# Qwiic_MP3.net
KiCad netlist of a schematic drawn in EAGLE
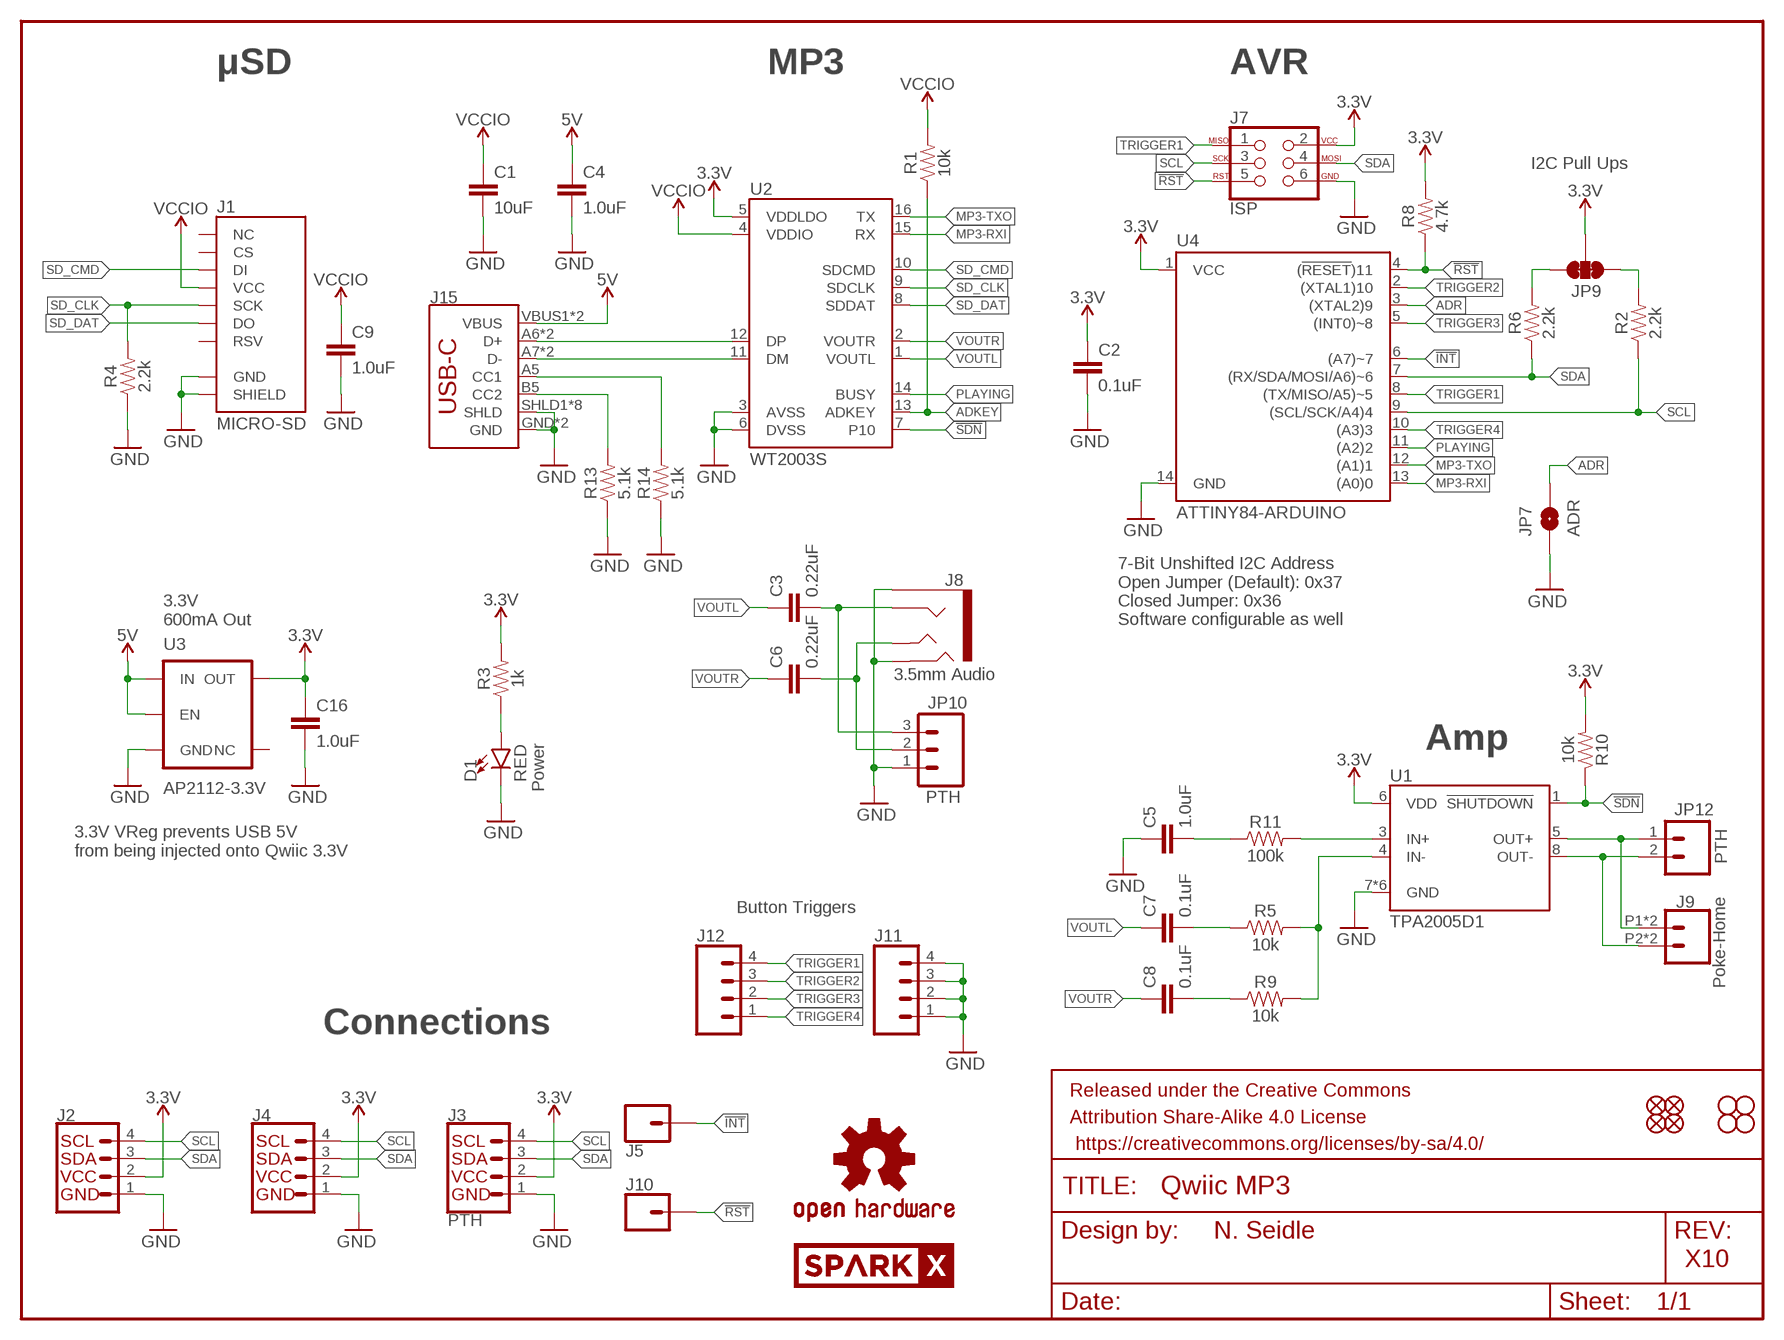
[diagram p0: schematic, sheet 1]

(export (version "E")
  (design (tool "Eeschema 10.0.6"))
  (components
    (comp (ref "C1")
      (value "10uF")
      (footprint "eagle-import:0603")
      (libsource (lib "eagle-import") (part "10UF-0603-6.3V-20%"))
    )
    (comp (ref "C2")
      (value "0.1uF")
      (footprint "eagle-import:0603")
      (libsource (lib "eagle-import") (part "0.1UF-0603-25V-(+80/-20%)"))
    )
    (comp (ref "C3")
      (value "0.22uF")
      (footprint "eagle-import:0603")
      (libsource (lib "eagle-import") (part "0.22UF-0603-25V-10%"))
    )
    (comp (ref "C4")
      (value "1.0uF")
      (footprint "eagle-import:0603")
      (libsource (lib "eagle-import") (part "1.0UF-0603-16V-10%"))
    )
    (comp (ref "C5")
      (value "1.0uF")
      (footprint "eagle-import:0603")
      (libsource (lib "eagle-import") (part "1.0UF-0603-16V-10%"))
    )
    (comp (ref "C6")
      (value "0.22uF")
      (footprint "eagle-import:0603")
      (libsource (lib "eagle-import") (part "0.22UF-0603-25V-10%"))
    )
    (comp (ref "C7")
      (value "0.1uF")
      (footprint "eagle-import:0603")
      (libsource (lib "eagle-import") (part "0.1UF-0603-25V-(+80/-20%)"))
    )
    (comp (ref "C8")
      (value "0.1uF")
      (footprint "eagle-import:0603")
      (libsource (lib "eagle-import") (part "0.1UF-0603-25V-(+80/-20%)"))
    )
    (comp (ref "C9")
      (value "1.0uF")
      (footprint "eagle-import:0603")
      (libsource (lib "eagle-import") (part "1.0UF-0603-16V-10%"))
    )
    (comp (ref "C16")
      (value "1.0uF")
      (footprint "eagle-import:0603")
      (libsource (lib "eagle-import") (part "1.0UF-0603-16V-10%"))
    )
    (comp (ref "D1")
      (value "RED")
      (footprint "eagle-import:LED-0603")
      (libsource (lib "eagle-import") (part "LED-RED0603"))
    )
    (comp (ref "FRAME1")
      (value "FRAME-LETTER")
      (footprint "eagle-import:CREATIVE_COMMONS")
      (libsource (lib "eagle-import") (part "FRAME-LETTER"))
    )
    (comp (ref "J1")
      (value "MICRO-SD")
      (footprint "eagle-import:MICRO-SD-SOCKET")
      (libsource (lib "eagle-import") (part "MICRO-SD_CARD_SOCKETPUSH-PUSH"))
    )
    (comp (ref "J2")
      (value "QWIIC_CONNECTORJS-1MM")
      (footprint "eagle-import:1X04_1MM_RA")
      (libsource (lib "eagle-import") (part "QWIIC_CONNECTORJS-1MM"))
    )
    (comp (ref "J3")
      (value "PTH")
      (footprint "eagle-import:1X04_NO_SILK")
      (libsource (lib "eagle-import") (part "I2C_STANDARD_NO_SILK"))
    )
    (comp (ref "J4")
      (value "QWIIC_CONNECTORJS-1MM")
      (footprint "eagle-import:1X04_1MM_RA")
      (libsource (lib "eagle-import") (part "QWIIC_CONNECTORJS-1MM"))
    )
    (comp (ref "J5")
      (value "CONN_01PTH_NO_SILK_YES_STOP")
      (footprint "eagle-import:1X01_NO_SILK")
      (libsource (lib "eagle-import") (part "CONN_01PTH_NO_SILK_YES_STOP"))
    )
    (comp (ref "J7")
      (value "ISP")
      (footprint "eagle-import:2X3_TEST_POINTS")
      (libsource (lib "eagle-import") (part "AVR_SPI_PROG_3X2TESTPOINTS"))
    )
    (comp (ref "J8")
      (value "3.5mm Audio")
      (footprint "eagle-import:AUDIO_JACK_3.5MM_TRRS_SMD_RA")
      (libsource (lib "eagle-import") (part "AUDIO_JACK_TRRSSMD_RA"))
    )
    (comp (ref "J9")
      (value "Poke-Home")
      (footprint "eagle-import:1X02_POKEHOME")
      (libsource (lib "eagle-import") (part "CONN_02SMALL_POKEHOME"))
    )
    (comp (ref "J10")
      (value "CONN_01PTH_NO_SILK_YES_STOP")
      (footprint "eagle-import:1X01_NO_SILK")
      (libsource (lib "eagle-import") (part "CONN_01PTH_NO_SILK_YES_STOP"))
    )
    (comp (ref "J11")
      (value "CONN_041X04_NO_SILK")
      (footprint "eagle-import:1X04_NO_SILK")
      (libsource (lib "eagle-import") (part "CONN_041X04_NO_SILK"))
    )
    (comp (ref "J12")
      (value "CONN_041X04_NO_SILK")
      (footprint "eagle-import:1X04_NO_SILK")
      (libsource (lib "eagle-import") (part "CONN_041X04_NO_SILK"))
    )
    (comp (ref "J15")
      (value "USB_C16PIN")
      (footprint "eagle-import:USB-C-16P")
      (libsource (lib "eagle-import") (part "USB_C16PIN"))
    )
    (comp (ref "JP1")
      (value "FIDUCIALUFIDUCIAL")
      (footprint "eagle-import:MICRO-FIDUCIAL")
      (libsource (lib "eagle-import") (part "FIDUCIALUFIDUCIAL"))
    )
    (comp (ref "JP2")
      (value "FIDUCIALUFIDUCIAL")
      (footprint "eagle-import:MICRO-FIDUCIAL")
      (libsource (lib "eagle-import") (part "FIDUCIALUFIDUCIAL"))
    )
    (comp (ref "JP3")
      (value "STAND-OFF")
      (footprint "eagle-import:STAND-OFF")
      (libsource (lib "eagle-import") (part "STAND-OFF"))
    )
    (comp (ref "JP4")
      (value "STAND-OFF")
      (footprint "eagle-import:STAND-OFF")
      (libsource (lib "eagle-import") (part "STAND-OFF"))
    )
    (comp (ref "JP5")
      (value "FIDUCIALUFIDUCIAL")
      (footprint "eagle-import:MICRO-FIDUCIAL")
      (libsource (lib "eagle-import") (part "FIDUCIALUFIDUCIAL"))
    )
    (comp (ref "JP6")
      (value "FIDUCIALUFIDUCIAL")
      (footprint "eagle-import:MICRO-FIDUCIAL")
      (libsource (lib "eagle-import") (part "FIDUCIALUFIDUCIAL"))
    )
    (comp (ref "JP7")
      (value "ADR")
      (footprint "eagle-import:SMT-JUMPER_2_NO_NO-SILK")
      (libsource (lib "eagle-import") (part "JUMPER-SMT_2_NO_NO-SILK"))
    )
    (comp (ref "JP9")
      (value "JUMPER-SMT_3_2-NC_TRACE_SILK")
      (footprint "eagle-import:SMT-JUMPER_3_2-NC_TRACE_SILK")
      (libsource (lib "eagle-import") (part "JUMPER-SMT_3_2-NC_TRACE_SILK"))
    )
    (comp (ref "JP10")
      (value "PTH")
      (footprint "eagle-import:1X03_NO_SILK")
      (libsource (lib "eagle-import") (part "CONN_031X03_NO_SILK"))
    )
    (comp (ref "JP11")
      (value "STAND-OFF")
      (footprint "eagle-import:STAND-OFF")
      (libsource (lib "eagle-import") (part "STAND-OFF"))
    )
    (comp (ref "JP12")
      (value "PTH")
      (footprint "eagle-import:1X02_NO_SILK")
      (libsource (lib "eagle-import") (part "CONN_021X02_NO_SILK"))
    )
    (comp (ref "JP13")
      (value "STAND-OFF")
      (footprint "eagle-import:STAND-OFF")
      (libsource (lib "eagle-import") (part "STAND-OFF"))
    )
    (comp (ref "LOGO1")
      (value "OSHW-LOGOMINI")
      (footprint "eagle-import:OSHW-LOGO-MINI")
      (libsource (lib "eagle-import") (part "OSHW-LOGOMINI"))
    )
    (comp (ref "R1")
      (value "10k")
      (footprint "eagle-import:0603")
      (libsource (lib "eagle-import") (part "10KOHM-0603-1/10W-1%"))
    )
    (comp (ref "R2")
      (value "2.2k")
      (footprint "eagle-import:0603")
      (libsource (lib "eagle-import") (part "2.2KOHM-0603-1/10W-1%"))
    )
    (comp (ref "R3")
      (value "1k")
      (footprint "eagle-import:0603")
      (libsource (lib "eagle-import") (part "1KOHM-0603-1/10W-1%"))
    )
    (comp (ref "R4")
      (value "2.2k")
      (footprint "eagle-import:0603")
      (libsource (lib "eagle-import") (part "2.2KOHM-0603-1/10W-1%"))
    )
    (comp (ref "R5")
      (value "10k")
      (footprint "eagle-import:0603")
      (libsource (lib "eagle-import") (part "10KOHM-0603-1/10W-1%"))
    )
    (comp (ref "R6")
      (value "2.2k")
      (footprint "eagle-import:0603")
      (libsource (lib "eagle-import") (part "2.2KOHM-0603-1/10W-1%"))
    )
    (comp (ref "R8")
      (value "4.7k")
      (footprint "eagle-import:0603")
      (libsource (lib "eagle-import") (part "4.7KOHM-0603-1/10W-1%"))
    )
    (comp (ref "R9")
      (value "10k")
      (footprint "eagle-import:0603")
      (libsource (lib "eagle-import") (part "10KOHM-0603-1/10W-1%"))
    )
    (comp (ref "R10")
      (value "10k")
      (footprint "eagle-import:0603")
      (libsource (lib "eagle-import") (part "10KOHM-0603-1/10W-1%"))
    )
    (comp (ref "R11")
      (value "100k")
      (footprint "eagle-import:0603")
      (libsource (lib "eagle-import") (part "100KOHM-0603-1/10W-1%"))
    )
    (comp (ref "R13")
      (value "5.1k")
      (footprint "eagle-import:0603")
      (libsource (lib "eagle-import") (part "5.1KOHM5.1KOHM-0603-1/10W-1%"))
    )
    (comp (ref "R14")
      (value "5.1k")
      (footprint "eagle-import:0603")
      (libsource (lib "eagle-import") (part "5.1KOHM5.1KOHM-0603-1/10W-1%"))
    )
    (comp (ref "U$1")
      (value "SPARKX-LOGO3")
      (footprint "eagle-import:SPARKX-SMALL")
      (libsource (lib "eagle-import") (part "SPARKX-LOGO3"))
    )
    (comp (ref "U$2")
      (value "SPARKX-LOGO4")
      (footprint "eagle-import:SPARKX-MEDIUM")
      (libsource (lib "eagle-import") (part "SPARKX-LOGO4"))
    )
    (comp (ref "U1")
      (value "TPA2005D1")
      (footprint "eagle-import:QFN-8_PAD")
      (libsource (lib "eagle-import") (part "TPA2005D1DRB"))
    )
    (comp (ref "U2")
      (value "WT2003S")
      (footprint "eagle-import:SO16")
      (libsource (lib "eagle-import") (part "WT2003S"))
    )
    (comp (ref "U3")
      (value "AP2112-3.3V")
      (footprint "eagle-import:SOT23-5")
      (libsource (lib "eagle-import") (part "V_REG_AP2112K-3.3V"))
    )
    (comp (ref "U4")
      (value "ATTINY84-ARDUINO")
      (footprint "eagle-import:SO14")
      (libsource (lib "eagle-import") (part "ATTINY84-ARDUINO"))
    )
  )
  (nets
    (net (code "1") (name "/~{INT}") (class "Default")
      (node (ref "J5") (pin "1") (pinfunction "1_1") (pintype "passive"))
      (node (ref "U4") (pin "6") (pinfunction "(A7)~{7}_6") (pintype "bidirectional"))
    )
    (net (code "2") (name "/~{RST}") (class "Default")
      (node (ref "J10") (pin "1") (pinfunction "1_1") (pintype "passive"))
      (node (ref "J7") (pin "5") (pinfunction "5_5") (pintype "passive"))
      (node (ref "R8") (pin "1") (pinfunction "1_1") (pintype "passive"))
      (node (ref "U4") (pin "4") (pinfunction "(~{RESET})11_4") (pintype "bidirectional"))
    )
    (net (code "3") (name "/~{SDN}") (class "Default")
      (node (ref "R10") (pin "1") (pinfunction "1_1") (pintype "passive"))
      (node (ref "U1") (pin "1") (pinfunction "~{SHUTDOWN}_1") (pintype "input"))
      (node (ref "U2") (pin "7") (pinfunction "P10_7") (pintype "bidirectional"))
    )
    (net (code "4") (name "3.3V") (class "Default")
      (node (ref "C16") (pin "1") (pinfunction "1_1") (pintype "passive"))
      (node (ref "C2") (pin "1") (pinfunction "1_1") (pintype "passive"))
      (node (ref "J2") (pin "2") (pinfunction "2_2") (pintype "power_in"))
      (node (ref "J3") (pin "2") (pinfunction "VCC_2") (pintype "power_in"))
      (node (ref "J4") (pin "2") (pinfunction "2_2") (pintype "power_in"))
      (node (ref "J7") (pin "2") (pinfunction "2_2") (pintype "passive"))
      (node (ref "JP9") (pin "2") (pinfunction "2_2") (pintype "passive"))
      (node (ref "R10") (pin "2") (pinfunction "2_2") (pintype "passive"))
      (node (ref "R3") (pin "2") (pinfunction "2_2") (pintype "passive"))
      (node (ref "R8") (pin "2") (pinfunction "2_2") (pintype "passive"))
      (node (ref "U1") (pin "6") (pinfunction "VDD_6") (pintype "power_in"))
      (node (ref "U2") (pin "5") (pinfunction "VDDLDO_5") (pintype "bidirectional"))
      (node (ref "U3") (pin "5") (pinfunction "OUT_5") (pintype "passive"))
      (node (ref "U4") (pin "1") (pinfunction "VCC_1") (pintype "bidirectional"))
    )
    (net (code "5") (name "5V") (class "Default")
      (node (ref "C4") (pin "1") (pinfunction "1_1") (pintype "passive"))
      (node (ref "J15") (pin "VBUS1") (pinfunction "VBUS_VBUS1") (pintype "bidirectional"))
      (node (ref "J15") (pin "VBUS2") (pinfunction "VBUS_VBUS2") (pintype "bidirectional"))
      (node (ref "U3") (pin "1") (pinfunction "IN_1") (pintype "input"))
      (node (ref "U3") (pin "3") (pinfunction "EN_3") (pintype "input"))
    )
    (net (code "6") (name "ADKEY") (class "Default")
      (node (ref "R1") (pin "1") (pinfunction "1_1") (pintype "passive"))
      (node (ref "U2") (pin "13") (pinfunction "ADKEY_13") (pintype "bidirectional"))
    )
    (net (code "7") (name "ADR") (class "Default")
      (node (ref "JP7") (pin "2") (pinfunction "2_2") (pintype "passive"))
      (node (ref "U4") (pin "3") (pinfunction "(XTAL2)9_3") (pintype "bidirectional"))
    )
    (net (code "8") (name "GND") (class "Default")
      (node (ref "C1") (pin "2") (pinfunction "2_2") (pintype "passive"))
      (node (ref "C16") (pin "2") (pinfunction "2_2") (pintype "passive"))
      (node (ref "C2") (pin "2") (pinfunction "2_2") (pintype "passive"))
      (node (ref "C4") (pin "2") (pinfunction "2_2") (pintype "passive"))
      (node (ref "C5") (pin "1") (pinfunction "1_1") (pintype "passive"))
      (node (ref "C9") (pin "2") (pinfunction "2_2") (pintype "passive"))
      (node (ref "D1") (pin "C") (pinfunction "C_C") (pintype "passive"))
      (node (ref "J1") (pin "CD1") (pinfunction "SHIELD_CD1") (pintype "bidirectional"))
      (node (ref "J1") (pin "GND") (pinfunction "GND_GND") (pintype "bidirectional"))
      (node (ref "J11") (pin "1") (pinfunction "1_1") (pintype "passive"))
      (node (ref "J11") (pin "2") (pinfunction "2_2") (pintype "passive"))
      (node (ref "J11") (pin "3") (pinfunction "3_3") (pintype "passive"))
      (node (ref "J11") (pin "4") (pinfunction "4_4") (pintype "passive"))
      (node (ref "J15") (pin "GND") (pinfunction "GND_GND") (pintype "bidirectional"))
      (node (ref "J15") (pin "GND2") (pinfunction "GND_GND2") (pintype "bidirectional"))
      (node (ref "J15") (pin "SHLD1") (pinfunction "SHLD_SHLD1") (pintype "bidirectional"))
      (node (ref "J15") (pin "SHLD2") (pinfunction "SHLD_SHLD2") (pintype "bidirectional"))
      (node (ref "J15") (pin "SHLD3") (pinfunction "SHLD_SHLD3") (pintype "bidirectional"))
      (node (ref "J15") (pin "SHLD4") (pinfunction "SHLD_SHLD4") (pintype "bidirectional"))
      (node (ref "J15") (pin "SHLD5") (pinfunction "SHLD_SHLD5") (pintype "bidirectional"))
      (node (ref "J15") (pin "SHLD6") (pinfunction "SHLD_SHLD6") (pintype "bidirectional"))
      (node (ref "J15") (pin "SHLD7") (pinfunction "SHLD_SHLD7") (pintype "bidirectional"))
      (node (ref "J15") (pin "SHLD8") (pinfunction "SHLD_SHLD8") (pintype "bidirectional"))
      (node (ref "J2") (pin "1") (pinfunction "1_1") (pintype "power_in"))
      (node (ref "J3") (pin "1") (pinfunction "GND_1") (pintype "power_in"))
      (node (ref "J4") (pin "1") (pinfunction "1_1") (pintype "power_in"))
      (node (ref "J7") (pin "6") (pinfunction "6_6") (pintype "passive"))
      (node (ref "J8") (pin "EARTH") (pinfunction "EARTH_EARTH") (pintype "bidirectional"))
      (node (ref "J8") (pin "RING2") (pinfunction "RING2_RING2") (pintype "bidirectional"))
      (node (ref "JP10") (pin "1") (pinfunction "1_1") (pintype "passive"))
      (node (ref "JP7") (pin "1") (pinfunction "1_1") (pintype "passive"))
      (node (ref "R13") (pin "1") (pinfunction "1_1") (pintype "passive"))
      (node (ref "R14") (pin "1") (pinfunction "1_1") (pintype "passive"))
      (node (ref "R4") (pin "1") (pinfunction "1_1") (pintype "passive"))
      (node (ref "U1") (pin "10") (pinfunction "GND_10") (pintype "power_in"))
      (node (ref "U1") (pin "11") (pinfunction "GND_11") (pintype "power_in"))
      (node (ref "U1") (pin "12") (pinfunction "GND_12") (pintype "power_in"))
      (node (ref "U1") (pin "13") (pinfunction "GND_13") (pintype "power_in"))
      (node (ref "U1") (pin "7") (pinfunction "GND_7") (pintype "power_in"))
      (node (ref "U1") (pin "9") (pinfunction "GND_9") (pintype "power_in"))
      (node (ref "U2") (pin "3") (pinfunction "AVSS_3") (pintype "bidirectional"))
      (node (ref "U2") (pin "6") (pinfunction "DVSS_6") (pintype "bidirectional"))
      (node (ref "U3") (pin "2") (pinfunction "GND_2") (pintype "input"))
      (node (ref "U4") (pin "14") (pinfunction "GND_14") (pintype "bidirectional"))
    )
    (net (code "9") (name "MP3-RXI") (class "Default")
      (node (ref "U2") (pin "15") (pinfunction "RX_15") (pintype "bidirectional"))
      (node (ref "U4") (pin "13") (pinfunction "(A0)0_13") (pintype "bidirectional"))
    )
    (net (code "10") (name "MP3-TXO") (class "Default")
      (node (ref "U2") (pin "16") (pinfunction "TX_16") (pintype "bidirectional"))
      (node (ref "U4") (pin "12") (pinfunction "(A1)1_12") (pintype "bidirectional"))
    )
    (net (code "11") (name "Net-(C3-Pad2)") (class "Default")
      (node (ref "C3") (pin "2") (pinfunction "2_2") (pintype "passive"))
      (node (ref "J8") (pin "RING1") (pinfunction "RING1_RING1") (pintype "bidirectional"))
      (node (ref "JP10") (pin "3") (pinfunction "3_3") (pintype "passive"))
    )
    (net (code "12") (name "Net-(C5-Pad2)") (class "Default")
      (node (ref "C5") (pin "2") (pinfunction "2_2") (pintype "passive"))
      (node (ref "R11") (pin "1") (pinfunction "1_1") (pintype "passive"))
    )
    (net (code "13") (name "Net-(C6-Pad2)") (class "Default")
      (node (ref "C6") (pin "2") (pinfunction "2_2") (pintype "passive"))
      (node (ref "J8") (pin "TIP") (pinfunction "TIP_TIP") (pintype "bidirectional"))
      (node (ref "JP10") (pin "2") (pinfunction "2_2") (pintype "passive"))
    )
    (net (code "14") (name "Net-(C7-Pad2)") (class "Default")
      (node (ref "C7") (pin "2") (pinfunction "2_2") (pintype "passive"))
      (node (ref "R5") (pin "1") (pinfunction "1_1") (pintype "passive"))
    )
    (net (code "15") (name "Net-(C8-Pad2)") (class "Default")
      (node (ref "C8") (pin "2") (pinfunction "2_2") (pintype "passive"))
      (node (ref "R9") (pin "1") (pinfunction "1_1") (pintype "passive"))
    )
    (net (code "16") (name "Net-(D1-PadA)") (class "Default")
      (node (ref "D1") (pin "A") (pinfunction "A_A") (pintype "passive"))
      (node (ref "R3") (pin "1") (pinfunction "1_1") (pintype "passive"))
    )
    (net (code "17") (name "Net-(J15-CC1)") (class "Default")
      (node (ref "J15") (pin "A5") (pinfunction "CC1_A5") (pintype "bidirectional"))
      (node (ref "R14") (pin "2") (pinfunction "2_2") (pintype "passive"))
    )
    (net (code "18") (name "Net-(J15-CC2)") (class "Default")
      (node (ref "J15") (pin "B5") (pinfunction "CC2_B5") (pintype "bidirectional"))
      (node (ref "R13") (pin "2") (pinfunction "2_2") (pintype "passive"))
    )
    (net (code "19") (name "Net-(JP9-Pad1)") (class "Default")
      (node (ref "JP9") (pin "1") (pinfunction "1_1") (pintype "passive"))
      (node (ref "R2") (pin "2") (pinfunction "2_2") (pintype "passive"))
    )
    (net (code "20") (name "Net-(JP9-Pad3)") (class "Default")
      (node (ref "JP9") (pin "3") (pinfunction "3_3") (pintype "passive"))
      (node (ref "R6") (pin "2") (pinfunction "2_2") (pintype "passive"))
    )
    (net (code "21") (name "Net-(U1-IN+)") (class "Default")
      (node (ref "R11") (pin "2") (pinfunction "2_2") (pintype "passive"))
      (node (ref "U1") (pin "3") (pinfunction "IN+_3") (pintype "bidirectional"))
    )
    (net (code "22") (name "Net-(U1-IN-)") (class "Default")
      (node (ref "R5") (pin "2") (pinfunction "2_2") (pintype "passive"))
      (node (ref "R9") (pin "2") (pinfunction "2_2") (pintype "passive"))
      (node (ref "U1") (pin "4") (pinfunction "IN-_4") (pintype "bidirectional"))
    )
    (net (code "23") (name "Net-(U1-OUT+)") (class "Default")
      (node (ref "J9") (pin "P1") (pinfunction "1_P1") (pintype "passive"))
      (node (ref "J9") (pin "P3") (pinfunction "1_P3") (pintype "passive"))
      (node (ref "JP12") (pin "1") (pinfunction "1_1") (pintype "passive"))
      (node (ref "U1") (pin "5") (pinfunction "OUT+_5") (pintype "bidirectional"))
    )
    (net (code "24") (name "Net-(U1-OUT-)") (class "Default")
      (node (ref "J9") (pin "P2") (pinfunction "2_P2") (pintype "passive"))
      (node (ref "J9") (pin "P4") (pinfunction "2_P4") (pintype "passive"))
      (node (ref "JP12") (pin "2") (pinfunction "2_2") (pintype "passive"))
      (node (ref "U1") (pin "8") (pinfunction "OUT-_8") (pintype "bidirectional"))
    )
    (net (code "25") (name "Net-(U2-DM)") (class "Default")
      (node (ref "J15") (pin "A7") (pinfunction "D-_A7") (pintype "bidirectional"))
      (node (ref "J15") (pin "B7") (pinfunction "D-_B7") (pintype "bidirectional"))
      (node (ref "U2") (pin "11") (pinfunction "DM_11") (pintype "bidirectional"))
    )
    (net (code "26") (name "Net-(U2-DP)") (class "Default")
      (node (ref "J15") (pin "A6") (pinfunction "D+_A6") (pintype "bidirectional"))
      (node (ref "J15") (pin "B6") (pinfunction "D+_B6") (pintype "bidirectional"))
      (node (ref "U2") (pin "12") (pinfunction "DP_12") (pintype "bidirectional"))
    )
    (net (code "27") (name "PLAYING") (class "Default")
      (node (ref "U2") (pin "14") (pinfunction "BUSY_14") (pintype "bidirectional"))
      (node (ref "U4") (pin "11") (pinfunction "(A2)2_11") (pintype "bidirectional"))
    )
    (net (code "28") (name "SCL") (class "Default")
      (node (ref "J2") (pin "4") (pinfunction "4_4") (pintype "passive"))
      (node (ref "J3") (pin "4") (pinfunction "SCL_4") (pintype "passive"))
      (node (ref "J4") (pin "4") (pinfunction "4_4") (pintype "passive"))
      (node (ref "J7") (pin "3") (pinfunction "3_3") (pintype "passive"))
      (node (ref "R2") (pin "1") (pinfunction "1_1") (pintype "passive"))
      (node (ref "U4") (pin "9") (pinfunction "(SCL/SCK/A4)4_9") (pintype "bidirectional"))
    )
    (net (code "29") (name "SDA") (class "Default")
      (node (ref "J2") (pin "3") (pinfunction "3_3") (pintype "passive"))
      (node (ref "J3") (pin "3") (pinfunction "SDA_3") (pintype "passive"))
      (node (ref "J4") (pin "3") (pinfunction "3_3") (pintype "passive"))
      (node (ref "J7") (pin "4") (pinfunction "4_4") (pintype "passive"))
      (node (ref "R6") (pin "1") (pinfunction "1_1") (pintype "passive"))
      (node (ref "U4") (pin "7") (pinfunction "(RX/SDA/MOSI/A6)~{6}_7") (pintype "bidirectional"))
    )
    (net (code "30") (name "SD_CLK") (class "Default")
      (node (ref "J1") (pin "SCLK") (pinfunction "SCK_SCLK") (pintype "bidirectional"))
      (node (ref "R4") (pin "2") (pinfunction "2_2") (pintype "passive"))
      (node (ref "U2") (pin "9") (pinfunction "SDCLK_9") (pintype "bidirectional"))
    )
    (net (code "31") (name "SD_CMD") (class "Default")
      (node (ref "J1") (pin "DI") (pinfunction "DI_DI") (pintype "bidirectional"))
      (node (ref "U2") (pin "10") (pinfunction "SDCMD_10") (pintype "bidirectional"))
    )
    (net (code "32") (name "SD_DAT") (class "Default")
      (node (ref "J1") (pin "DO") (pinfunction "DO_DO") (pintype "bidirectional"))
      (node (ref "U2") (pin "8") (pinfunction "SDDAT_8") (pintype "bidirectional"))
    )
    (net (code "33") (name "TRIGGER1") (class "Default")
      (node (ref "J12") (pin "4") (pinfunction "4_4") (pintype "passive"))
      (node (ref "J7") (pin "1") (pinfunction "1_1") (pintype "passive"))
      (node (ref "U4") (pin "8") (pinfunction "(TX/MISO/A5)~{5}_8") (pintype "bidirectional"))
    )
    (net (code "34") (name "TRIGGER2") (class "Default")
      (node (ref "J12") (pin "3") (pinfunction "3_3") (pintype "passive"))
      (node (ref "U4") (pin "2") (pinfunction "(XTAL1)10_2") (pintype "bidirectional"))
    )
    (net (code "35") (name "TRIGGER3") (class "Default")
      (node (ref "J12") (pin "2") (pinfunction "2_2") (pintype "passive"))
      (node (ref "U4") (pin "5") (pinfunction "(INT0)~{8}_5") (pintype "bidirectional"))
    )
    (net (code "36") (name "TRIGGER4") (class "Default")
      (node (ref "J12") (pin "1") (pinfunction "1_1") (pintype "passive"))
      (node (ref "U4") (pin "10") (pinfunction "(A3)3_10") (pintype "bidirectional"))
    )
    (net (code "37") (name "VCCIO") (class "Default")
      (node (ref "C1") (pin "1") (pinfunction "1_1") (pintype "passive"))
      (node (ref "C9") (pin "1") (pinfunction "1_1") (pintype "passive"))
      (node (ref "J1") (pin "VCC") (pinfunction "VCC_VCC") (pintype "bidirectional"))
      (node (ref "R1") (pin "2") (pinfunction "2_2") (pintype "passive"))
      (node (ref "U2") (pin "4") (pinfunction "VDDIO_4") (pintype "bidirectional"))
    )
    (net (code "38") (name "VOUTL") (class "Default")
      (node (ref "C3") (pin "1") (pinfunction "1_1") (pintype "passive"))
      (node (ref "C7") (pin "1") (pinfunction "1_1") (pintype "passive"))
      (node (ref "U2") (pin "1") (pinfunction "VOUTL_1") (pintype "bidirectional"))
    )
    (net (code "39") (name "VOUTR") (class "Default")
      (node (ref "C6") (pin "1") (pinfunction "1_1") (pintype "passive"))
      (node (ref "C8") (pin "1") (pinfunction "1_1") (pintype "passive"))
      (node (ref "U2") (pin "2") (pinfunction "VOUTR_2") (pintype "bidirectional"))
    )
    (net (code "40") (name "unconnected-(J1-NC-PadRSV2)") (class "Default")
      (node (ref "J1") (pin "RSV2") (pinfunction "NC_RSV2") (pintype "bidirectional"))
    )
    (net (code "41") (name "unconnected-(J1-PadCS)") (class "Default")
      (node (ref "J1") (pin "CS") (pinfunction "CS_CS") (pintype "bidirectional"))
    )
    (net (code "42") (name "unconnected-(J1-RSV-PadRSV1)") (class "Default")
      (node (ref "J1") (pin "RSV1") (pinfunction "RSV_RSV1") (pintype "bidirectional"))
    )
    (net (code "43") (name "unconnected-(U3-NC-Pad4)") (class "Default")
      (node (ref "U3") (pin "4") (pinfunction "NC_4") (pintype "input"))
    )
  )
)
